# MicroMod-Ethernet-Function-Board-W5500.net
KiCad netlist of a schematic drawn in EAGLE
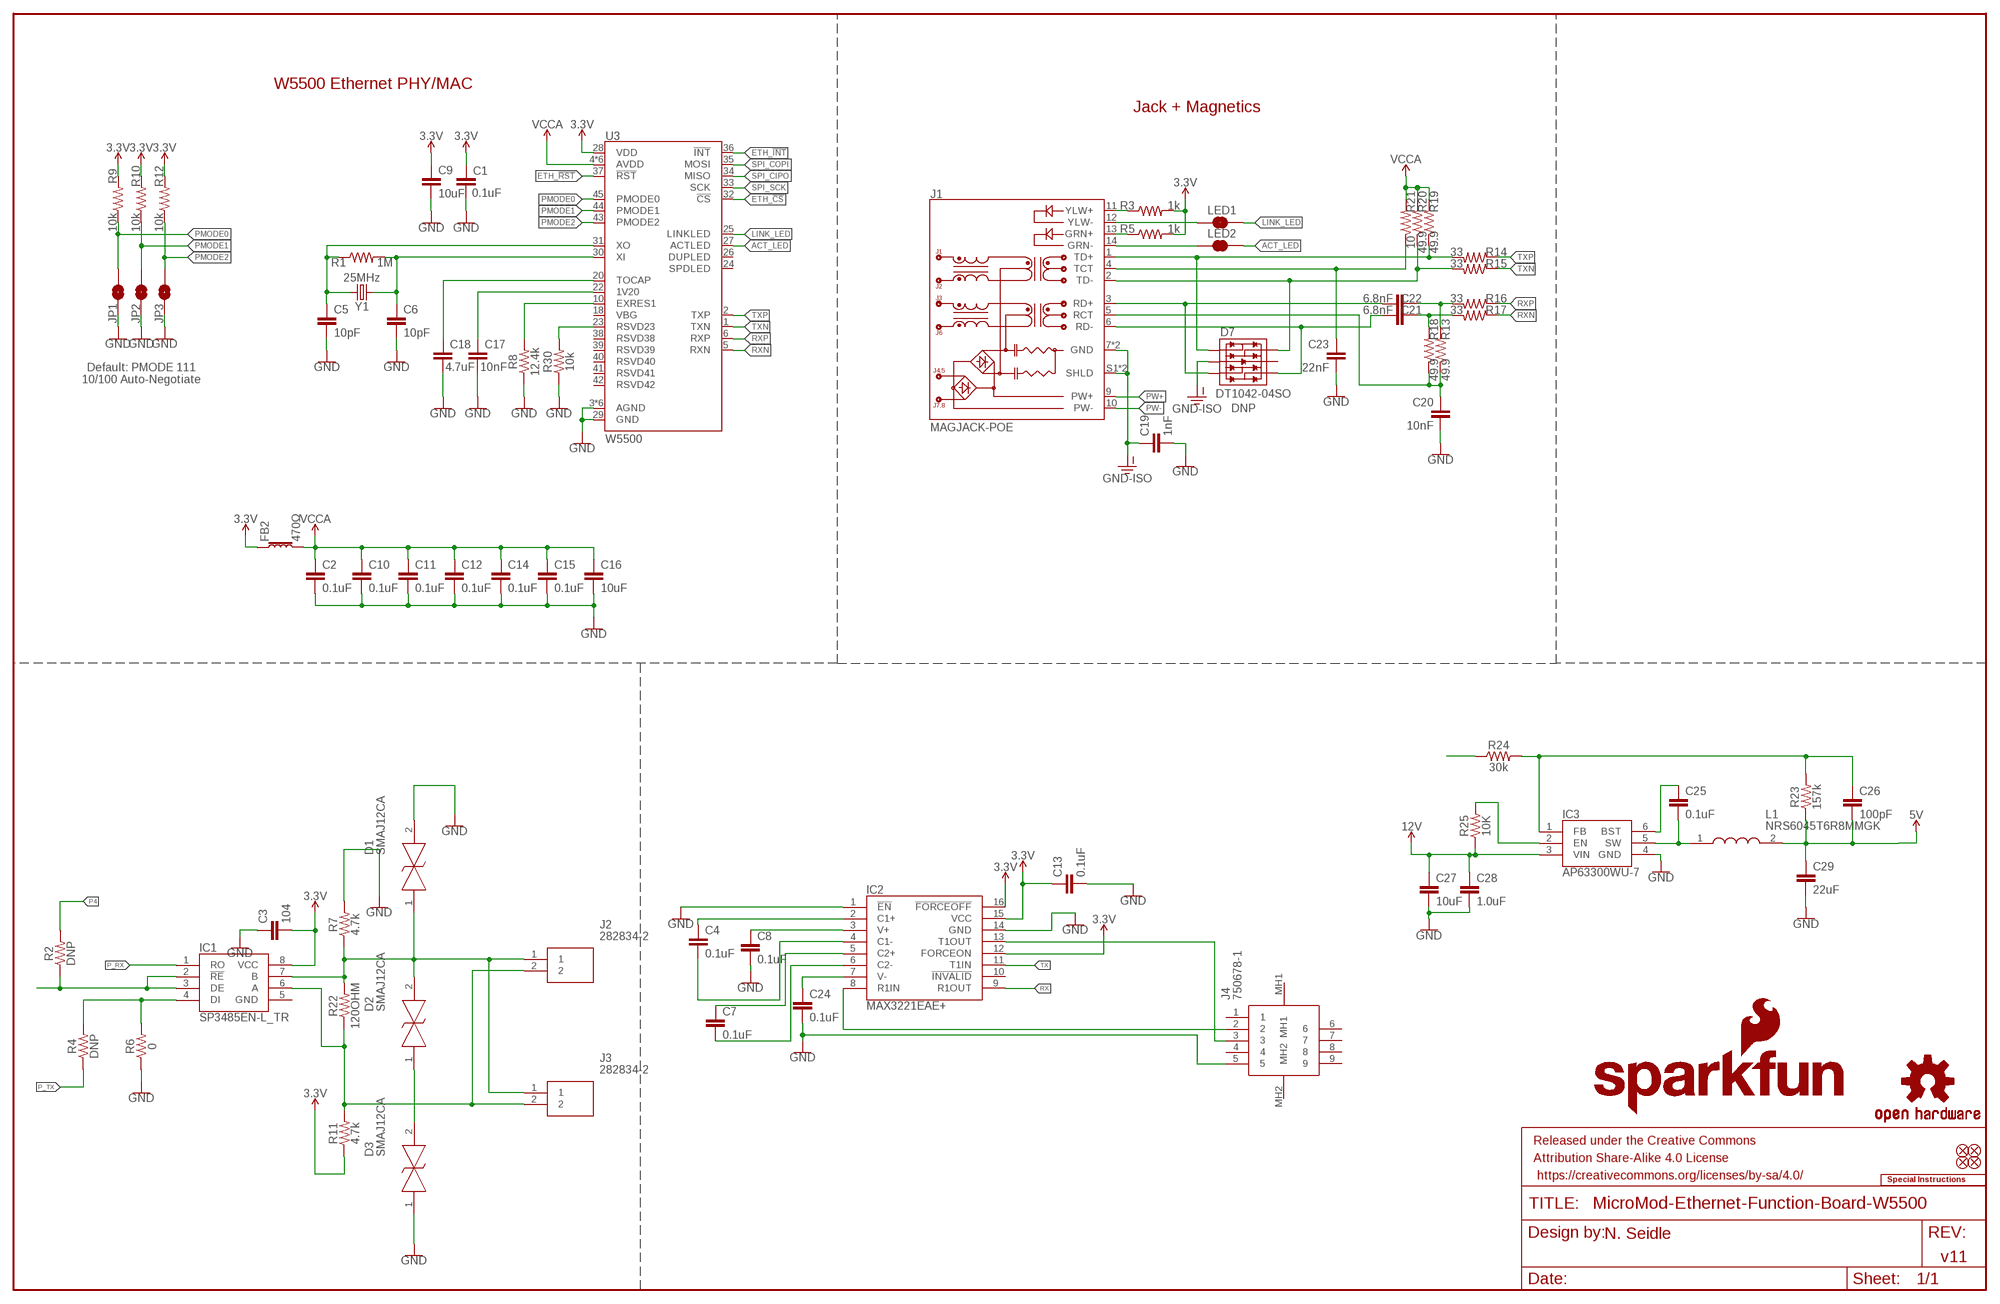
[diagram p0: schematic, sheet 1]

(export (version "E")
  (design (tool "Eeschema 10.0.6"))
  (components
    (comp (ref "C1")
      (value "0.1uF")
      (footprint "eagle-import:0603")
      (libsource (lib "eagle-import") (part "0.1UF-0603-25V-(+80/-20%)"))
    )
    (comp (ref "C2")
      (value "0.1uF")
      (footprint "eagle-import:0603")
      (libsource (lib "eagle-import") (part "0.1UF-0603-25V-5%"))
    )
    (comp (ref "C3")
      (value "104")
      (footprint "eagle-import:0402-TIGHT_NO_CREAM")
      (libsource (lib "eagle-import") (part "DNP-0402-TIGHT_NO_CREAM"))
    )
    (comp (ref "C4")
      (value "0.1uF")
      (footprint "eagle-import:0402-TIGHT")
      (libsource (lib "eagle-import") (part "0.1UF-0402T-10V-10%-X7R"))
    )
    (comp (ref "C5")
      (value "10pF")
      (footprint "eagle-import:0603")
      (libsource (lib "eagle-import") (part "10PF-0603-50V-5%"))
    )
    (comp (ref "C6")
      (value "10pF")
      (footprint "eagle-import:0603")
      (libsource (lib "eagle-import") (part "10PF-0603-50V-5%"))
    )
    (comp (ref "C7")
      (value "0.1uF")
      (footprint "eagle-import:0402-TIGHT")
      (libsource (lib "eagle-import") (part "0.1UF-0402T-10V-10%-X7R"))
    )
    (comp (ref "C8")
      (value "0.1uF")
      (footprint "eagle-import:0402-TIGHT")
      (libsource (lib "eagle-import") (part "0.1UF-0402T-10V-10%-X7R"))
    )
    (comp (ref "C9")
      (value "10uF")
      (footprint "eagle-import:0603")
      (libsource (lib "eagle-import") (part "10UF-0603-6.3V-20%"))
    )
    (comp (ref "C10")
      (value "0.1uF")
      (footprint "eagle-import:0603")
      (libsource (lib "eagle-import") (part "0.1UF-0603-25V-5%"))
    )
    (comp (ref "C11")
      (value "0.1uF")
      (footprint "eagle-import:0603")
      (libsource (lib "eagle-import") (part "0.1UF-0603-25V-5%"))
    )
    (comp (ref "C12")
      (value "0.1uF")
      (footprint "eagle-import:0603")
      (libsource (lib "eagle-import") (part "0.1UF-0603-25V-5%"))
    )
    (comp (ref "C13")
      (value "0.1uF")
      (footprint "eagle-import:0402-TIGHT")
      (libsource (lib "eagle-import") (part "0.1UF-0402T-10V-10%-X7R"))
    )
    (comp (ref "C14")
      (value "0.1uF")
      (footprint "eagle-import:0603")
      (libsource (lib "eagle-import") (part "0.1UF-0603-25V-5%"))
    )
    (comp (ref "C15")
      (value "0.1uF")
      (footprint "eagle-import:0603")
      (libsource (lib "eagle-import") (part "0.1UF-0603-25V-5%"))
    )
    (comp (ref "C16")
      (value "10uF")
      (footprint "eagle-import:0603")
      (libsource (lib "eagle-import") (part "10UF-0603-6.3V-20%"))
    )
    (comp (ref "C17")
      (value "10nF")
      (footprint "eagle-import:0603")
      (libsource (lib "eagle-import") (part "10NF-0603-50V-10%"))
    )
    (comp (ref "C18")
      (value "4.7uF")
      (footprint "eagle-import:0603")
      (libsource (lib "eagle-import") (part "4.7UF-0603-6.3V-(10%)"))
    )
    (comp (ref "C19")
      (value "1nF")
      (footprint "eagle-import:1206")
      (libsource (lib "eagle-import") (part "1.0NF/1000PF-1206-2KV-10%"))
    )
    (comp (ref "C20")
      (value "10nF")
      (footprint "eagle-import:0603")
      (libsource (lib "eagle-import") (part "10NF-0603-50V-10%"))
    )
    (comp (ref "C21")
      (value "6.8nF")
      (footprint "eagle-import:0603")
      (libsource (lib "eagle-import") (part "6.8NF/6800PF-0603-50V-5%"))
    )
    (comp (ref "C22")
      (value "6.8nF")
      (footprint "eagle-import:0603")
      (libsource (lib "eagle-import") (part "6.8NF/6800PF-0603-50V-5%"))
    )
    (comp (ref "C23")
      (value "22nF")
      (footprint "eagle-import:0603")
      (libsource (lib "eagle-import") (part "22NF/22,000PF-0603-50V-10%"))
    )
    (comp (ref "C24")
      (value "0.1uF")
      (footprint "eagle-import:0402-TIGHT")
      (libsource (lib "eagle-import") (part "0.1UF-0402T-10V-10%-X7R"))
    )
    (comp (ref "C25")
      (value "0.1uF")
      (footprint "eagle-import:0402-TIGHT")
      (libsource (lib "eagle-import") (part "0.1UF-0402T-10V-10%-X7R"))
    )
    (comp (ref "C26")
      (value "100pF")
      (footprint "eagle-import:0402-TIGHT")
      (libsource (lib "eagle-import") (part "100PF-0402T-50V-5%"))
    )
    (comp (ref "C27")
      (value "10uF")
      (footprint "eagle-import:0402-TIGHT")
      (libsource (lib "eagle-import") (part "10UF-0402T-6.3V-20%"))
    )
    (comp (ref "C28")
      (value "1.0uF")
      (footprint "eagle-import:0402-TIGHT")
      (libsource (lib "eagle-import") (part "1.0UF-0402T-16V-10%"))
    )
    (comp (ref "C29")
      (value "22uF")
      (footprint "eagle-import:0603")
      (libsource (lib "eagle-import") (part "22UF-0603-6.3V-20%"))
    )
    (comp (ref "D1")
      (value "SMAJ12CA")
      (footprint "eagle-import:DIONM5026X229N")
      (fields (field (name "MOUSER_PART_NUMBER") "576-SMAJ12CA"))
      (libsource (lib "eagle-import") (part "SMAJ12CA"))
    )
    (comp (ref "D2")
      (value "SMAJ12CA")
      (footprint "eagle-import:DIONM5026X229N")
      (fields (field (name "MOUSER_PART_NUMBER") "576-SMAJ12CA"))
      (libsource (lib "eagle-import") (part "SMAJ12CA"))
    )
    (comp (ref "D3")
      (value "SMAJ12CA")
      (footprint "eagle-import:DIONM5026X229N")
      (fields (field (name "MOUSER_PART_NUMBER") "576-SMAJ12CA"))
      (libsource (lib "eagle-import") (part "SMAJ12CA"))
    )
    (comp (ref "D7")
      (value "DT1042-04SO")
      (footprint "eagle-import:SOT-23-6")
      (libsource (lib "eagle-import") (part "TVS_DIODE_ARRAYSMD"))
    )
    (comp (ref "FB2")
      (value "470Ω")
      (footprint "eagle-import:0603")
      (libsource (lib "eagle-import") (part "FERRITE_BEAD-0603-470Ω-100MHZ-1A-200MILIΩ"))
    )
    (comp (ref "FD1")
      (value "FIDUCIALUFIDUCIAL")
      (footprint "eagle-import:FIDUCIAL-MICRO")
      (libsource (lib "eagle-import") (part "FIDUCIALUFIDUCIAL"))
    )
    (comp (ref "FD2")
      (value "FIDUCIALUFIDUCIAL")
      (footprint "eagle-import:FIDUCIAL-MICRO")
      (libsource (lib "eagle-import") (part "FIDUCIALUFIDUCIAL"))
    )
    (comp (ref "FD3")
      (value "FIDUCIALUFIDUCIAL")
      (footprint "eagle-import:FIDUCIAL-MICRO")
      (libsource (lib "eagle-import") (part "FIDUCIALUFIDUCIAL"))
    )
    (comp (ref "FD4")
      (value "FIDUCIALUFIDUCIAL")
      (footprint "eagle-import:FIDUCIAL-MICRO")
      (libsource (lib "eagle-import") (part "FIDUCIALUFIDUCIAL"))
    )
    (comp (ref "FRAME1")
      (value "FRAME-LEDGER")
      (footprint "eagle-import:CREATIVE_COMMONS")
      (libsource (lib "eagle-import") (part "FRAME-LEDGER"))
    )
    (comp (ref "IC1")
      (value "SP3485EN-L_TR")
      (footprint "eagle-import:SOIC127P600X175-8N")
      (fields
        (field (name "ARROW_PART_NUMBER") "SP3485EN-L/TR")
        (field (name "MOUSER_PART_NUMBER") "701-SP3485EN-L/TR")
      )
      (libsource (lib "eagle-import") (part "SP3485EN-L_TR"))
    )
    (comp (ref "IC2")
      (value "MAX3221EAE+")
      (footprint "eagle-import:SOP65P778X199-16N")
      (fields (field (name "MOUSER_PART_NUMBER") "700-MAX3221EAE"))
      (libsource (lib "eagle-import") (part "MAX3221EAE+"))
    )
    (comp (ref "IC3")
      (value "AP63300WU-7")
      (footprint "eagle-import:SOT95P280X90-6N")
      (fields (field (name "MOUSER_PART_NUMBER") "621-AP63300WU-7"))
      (libsource (lib "eagle-import") (part "AP63300WU-7"))
    )
    (comp (ref "J1")
      (value "MAGJACK-POE")
      (footprint "eagle-import:MAGJACK-SYM_LED")
      (libsource (lib "eagle-import") (part "MAGJACK-POE"))
    )
    (comp (ref "J2")
      (value "282834-2")
      (footprint "eagle-import:282834-2_1")
      (fields (field (name "MOUSER_PART_NUMBER") "571-282834-2"))
      (libsource (lib "eagle-import") (part "282834-2"))
    )
    (comp (ref "J3")
      (value "282834-2")
      (footprint "eagle-import:282834-2_1")
      (fields (field (name "MOUSER_PART_NUMBER") "571-282834-2"))
      (libsource (lib "eagle-import") (part "282834-2"))
    )
    (comp (ref "J4")
      (value "750678-1")
      (footprint "eagle-import:7506781")
      (fields (field (name "MOUSER_PART_NUMBER") "571-7506781"))
      (libsource (lib "eagle-import") (part "750678-1"))
    )
    (comp (ref "JP1")
      (value "JUMPER-SMT_2_NO_SILK")
      (footprint "eagle-import:SMT-JUMPER_2_NO_SILK")
      (libsource (lib "eagle-import") (part "JUMPER-SMT_2_NO_SILK"))
    )
    (comp (ref "JP2")
      (value "JUMPER-SMT_2_NO_SILK")
      (footprint "eagle-import:SMT-JUMPER_2_NO_SILK")
      (libsource (lib "eagle-import") (part "JUMPER-SMT_2_NO_SILK"))
    )
    (comp (ref "JP3")
      (value "JUMPER-SMT_2_NO_SILK")
      (footprint "eagle-import:SMT-JUMPER_2_NO_SILK")
      (libsource (lib "eagle-import") (part "JUMPER-SMT_2_NO_SILK"))
    )
    (comp (ref "L1")
      (value "NRS6045T6R8MMGK")
      (footprint "eagle-import:NRS6045T6R8MMGK")
      (fields (field (name "MOUSER_PART_NUMBER") "963-NRS6045T6R8MMGK"))
      (libsource (lib "eagle-import") (part "NRS6045T6R8MMGK"))
    )
    (comp (ref "LED1")
      (value "JUMPER-SMT_2_NC_TRACE_SILK")
      (footprint "eagle-import:SMT-JUMPER_2_NC_TRACE_SILK")
      (libsource (lib "eagle-import") (part "JUMPER-SMT_2_NC_TRACE_SILK"))
    )
    (comp (ref "LED2")
      (value "JUMPER-SMT_2_NC_TRACE_SILK")
      (footprint "eagle-import:SMT-JUMPER_2_NC_TRACE_SILK")
      (libsource (lib "eagle-import") (part "JUMPER-SMT_2_NC_TRACE_SILK"))
    )
    (comp (ref "LOGO1")
      (value "SFE_LOGO_NAME_FLAME.1_INCH")
      (footprint "eagle-import:SFE_LOGO_NAME_FLAME_.1")
      (libsource (lib "eagle-import") (part "SFE_LOGO_NAME_FLAME.1_INCH"))
    )
    (comp (ref "LOGO2")
      (value "SPECIAL_INSTRUCTIONS-ORDERING")
      (footprint "eagle-import:ORDERING_INSTRUCTIONS")
      (libsource (lib "eagle-import") (part "SPECIAL_INSTRUCTIONS-ORDERING"))
    )
    (comp (ref "LOGO3")
      (value "OSHW-LOGOMINI")
      (footprint "eagle-import:OSHW-LOGO-MINI")
      (libsource (lib "eagle-import") (part "OSHW-LOGOMINI"))
    )
    (comp (ref "R1")
      (value "1M")
      (footprint "eagle-import:0603")
      (libsource (lib "eagle-import") (part "1MOHM-0603-1/4W-5%"))
    )
    (comp (ref "R2")
      (value "DNP")
      (footprint "eagle-import:0402-TIGHT")
      (libsource (lib "eagle-import") (part "DNP-0402T"))
    )
    (comp (ref "R3")
      (value "1k")
      (footprint "eagle-import:0603")
      (libsource (lib "eagle-import") (part "1KOHM-0603-1/10W-1%"))
    )
    (comp (ref "R4")
      (value "DNP")
      (footprint "eagle-import:0402-TIGHT")
      (libsource (lib "eagle-import") (part "DNP-0402T"))
    )
    (comp (ref "R5")
      (value "1k")
      (footprint "eagle-import:0603")
      (libsource (lib "eagle-import") (part "1KOHM-0603-1/10W-1%"))
    )
    (comp (ref "R6")
      (value "0")
      (footprint "eagle-import:0402-TIGHT")
      (libsource (lib "eagle-import") (part "0OHM-0402T-1/10W"))
    )
    (comp (ref "R7")
      (value "4.7k")
      (footprint "eagle-import:0402-TIGHT")
      (libsource (lib "eagle-import") (part "4.7KOHM-0402T-1/16W-1%"))
    )
    (comp (ref "R8")
      (value "12.4k")
      (footprint "eagle-import:0603")
      (libsource (lib "eagle-import") (part "12.4KOHM-0603-1/10W-1%"))
    )
    (comp (ref "R9")
      (value "10k")
      (footprint "eagle-import:0603")
      (libsource (lib "eagle-import") (part "10KOHM-0603-1/10W-1%"))
    )
    (comp (ref "R10")
      (value "10k")
      (footprint "eagle-import:0603")
      (libsource (lib "eagle-import") (part "10KOHM-0603-1/10W-1%"))
    )
    (comp (ref "R11")
      (value "4.7k")
      (footprint "eagle-import:0402-TIGHT")
      (libsource (lib "eagle-import") (part "4.7KOHM-0402T-1/16W-1%"))
    )
    (comp (ref "R12")
      (value "10k")
      (footprint "eagle-import:0603")
      (libsource (lib "eagle-import") (part "10KOHM-0603-1/10W-1%"))
    )
    (comp (ref "R13")
      (value "49.9")
      (footprint "eagle-import:0603")
      (libsource (lib "eagle-import") (part "49.9OHM-0603-1/10W-1%"))
    )
    (comp (ref "R14")
      (value "33")
      (footprint "eagle-import:0603")
      (libsource (lib "eagle-import") (part "33OHM-0603-1/10W-1%"))
    )
    (comp (ref "R15")
      (value "33")
      (footprint "eagle-import:0603")
      (libsource (lib "eagle-import") (part "33OHM-0603-1/10W-1%"))
    )
    (comp (ref "R16")
      (value "33")
      (footprint "eagle-import:0603")
      (libsource (lib "eagle-import") (part "33OHM-0603-1/10W-1%"))
    )
    (comp (ref "R17")
      (value "33")
      (footprint "eagle-import:0603")
      (libsource (lib "eagle-import") (part "33OHM-0603-1/10W-1%"))
    )
    (comp (ref "R18")
      (value "49.9")
      (footprint "eagle-import:0603")
      (libsource (lib "eagle-import") (part "49.9OHM-0603-1/10W-1%"))
    )
    (comp (ref "R19")
      (value "49.9")
      (footprint "eagle-import:0603")
      (libsource (lib "eagle-import") (part "49.9OHM-0603-1/10W-1%"))
    )
    (comp (ref "R20")
      (value "49.9")
      (footprint "eagle-import:0603")
      (libsource (lib "eagle-import") (part "49.9OHM-0603-1/10W-1%"))
    )
    (comp (ref "R21")
      (value "10")
      (footprint "eagle-import:0603")
      (libsource (lib "eagle-import") (part "10OHM-0603-1/10W-1%"))
    )
    (comp (ref "R22")
      (value "120OHM")
      (footprint "eagle-import:0603")
      (libsource (lib "eagle-import") (part "120OHM"))
    )
    (comp (ref "R23")
      (value "157k")
      (footprint "eagle-import:0402-TIGHT")
      (libsource (lib "eagle-import") (part "DNP-0402T"))
    )
    (comp (ref "R24")
      (value "30k")
      (footprint "eagle-import:0402-TIGHT")
      (libsource (lib "eagle-import") (part "DNP-0402T"))
    )
    (comp (ref "R25")
      (value "10K")
      (footprint "eagle-import:0402-TIGHT")
      (libsource (lib "eagle-import") (part "10KOHM-0402-1/10W-0.1%"))
    )
    (comp (ref "R30")
      (value "10k")
      (footprint "eagle-import:0603")
      (libsource (lib "eagle-import") (part "10KOHM-0603-1/10W-1%"))
    )
    (comp (ref "U3")
      (value "W5500")
      (footprint "eagle-import:LQFP-48")
      (libsource (lib "eagle-import") (part "W5500"))
    )
    (comp (ref "Y1")
      (value "25MHz")
      (footprint "eagle-import:CRYSTAL-SMD-2.0X1.6MM")
      (libsource (lib "eagle-import") (part "CRYSTAL-25MHZ-SMD-2.0X1.6MM"))
    )
  )
  (nets
    (net (code "1") (name "/ETH_~{CS}") (class "Default")
      (node (ref "U3") (pin "32") (pinfunction "~{CS}_32") (pintype "bidirectional"))
    )
    (net (code "2") (name "/ETH_~{INT}") (class "Default")
      (node (ref "U3") (pin "36") (pinfunction "~{INT}_36") (pintype "bidirectional"))
    )
    (net (code "3") (name "/ETH_~{RST}") (class "Default")
      (node (ref "U3") (pin "37") (pinfunction "~{RST}_37") (pintype "bidirectional"))
    )
    (net (code "4") (name "3.3V") (class "Default")
      (node (ref "C1") (pin "1") (pinfunction "1_1") (pintype "passive"))
      (node (ref "C13") (pin "1") (pinfunction "1_1") (pintype "passive"))
      (node (ref "C3") (pin "2") (pinfunction "2_2") (pintype "passive"))
      (node (ref "C9") (pin "1") (pinfunction "1_1") (pintype "passive"))
      (node (ref "FB2") (pin "1") (pinfunction "1_1") (pintype "passive"))
      (node (ref "IC1") (pin "8") (pinfunction "VCC_8") (pintype "bidirectional"))
      (node (ref "IC2") (pin "12") (pinfunction "FORCEON_12") (pintype "bidirectional"))
      (node (ref "IC2") (pin "15") (pinfunction "VCC_15") (pintype "bidirectional"))
      (node (ref "IC2") (pin "16") (pinfunction "~{FORCEOFF}_16") (pintype "bidirectional"))
      (node (ref "R10") (pin "2") (pinfunction "2_2") (pintype "passive"))
      (node (ref "R11") (pin "1") (pinfunction "1_1") (pintype "passive"))
      (node (ref "R12") (pin "2") (pinfunction "2_2") (pintype "passive"))
      (node (ref "R3") (pin "2") (pinfunction "2_2") (pintype "passive"))
      (node (ref "R5") (pin "2") (pinfunction "2_2") (pintype "passive"))
      (node (ref "R9") (pin "2") (pinfunction "2_2") (pintype "passive"))
      (node (ref "U3") (pin "28") (pinfunction "VDD_28") (pintype "bidirectional"))
    )
    (net (code "5") (name "5V") (class "Default")
      (node (ref "C26") (pin "2") (pinfunction "2_2") (pintype "passive"))
      (node (ref "C29") (pin "1") (pinfunction "1_1") (pintype "passive"))
      (node (ref "L1") (pin "2") (pinfunction "2_2") (pintype "bidirectional"))
      (node (ref "R23") (pin "1") (pinfunction "1_1") (pintype "passive"))
    )
    (net (code "6") (name "12V") (class "Default")
      (node (ref "C27") (pin "1") (pinfunction "1_1") (pintype "passive"))
      (node (ref "C28") (pin "1") (pinfunction "1_1") (pintype "passive"))
      (node (ref "IC3") (pin "3") (pinfunction "VIN_3") (pintype "bidirectional"))
      (node (ref "R25") (pin "1") (pinfunction "1_1") (pintype "passive"))
    )
    (net (code "7") (name "ACT_LED") (class "Default")
      (node (ref "LED2") (pin "2") (pinfunction "2_2") (pintype "passive"))
      (node (ref "U3") (pin "27") (pinfunction "ACTLED_27") (pintype "bidirectional"))
    )
    (net (code "8") (name "GND") (class "Default")
      (node (ref "C1") (pin "2") (pinfunction "2_2") (pintype "passive"))
      (node (ref "C10") (pin "2") (pinfunction "2_2") (pintype "passive"))
      (node (ref "C11") (pin "2") (pinfunction "2_2") (pintype "passive"))
      (node (ref "C12") (pin "2") (pinfunction "2_2") (pintype "passive"))
      (node (ref "C13") (pin "2") (pinfunction "2_2") (pintype "passive"))
      (node (ref "C14") (pin "2") (pinfunction "2_2") (pintype "passive"))
      (node (ref "C15") (pin "2") (pinfunction "2_2") (pintype "passive"))
      (node (ref "C16") (pin "2") (pinfunction "2_2") (pintype "passive"))
      (node (ref "C17") (pin "2") (pinfunction "2_2") (pintype "passive"))
      (node (ref "C18") (pin "2") (pinfunction "2_2") (pintype "passive"))
      (node (ref "C19") (pin "2") (pinfunction "2_2") (pintype "passive"))
      (node (ref "C2") (pin "2") (pinfunction "2_2") (pintype "passive"))
      (node (ref "C20") (pin "2") (pinfunction "2_2") (pintype "passive"))
      (node (ref "C23") (pin "2") (pinfunction "2_2") (pintype "passive"))
      (node (ref "C24") (pin "2") (pinfunction "2_2") (pintype "passive"))
      (node (ref "C27") (pin "2") (pinfunction "2_2") (pintype "passive"))
      (node (ref "C28") (pin "2") (pinfunction "2_2") (pintype "passive"))
      (node (ref "C29") (pin "2") (pinfunction "2_2") (pintype "passive"))
      (node (ref "C3") (pin "1") (pinfunction "1_1") (pintype "passive"))
      (node (ref "C5") (pin "2") (pinfunction "2_2") (pintype "passive"))
      (node (ref "C6") (pin "2") (pinfunction "2_2") (pintype "passive"))
      (node (ref "C8") (pin "2") (pinfunction "2_2") (pintype "passive"))
      (node (ref "C9") (pin "2") (pinfunction "2_2") (pintype "passive"))
      (node (ref "D1") (pin "2") (pinfunction "2_2") (pintype "bidirectional"))
      (node (ref "D3") (pin "1") (pinfunction "1_1") (pintype "bidirectional"))
      (node (ref "IC2") (pin "1") (pinfunction "~{EN}_1") (pintype "bidirectional"))
      (node (ref "IC2") (pin "14") (pinfunction "GND_14") (pintype "bidirectional"))
      (node (ref "IC3") (pin "4") (pinfunction "GND_4") (pintype "bidirectional"))
      (node (ref "J4") (pin "5") (pinfunction "5_5") (pintype "bidirectional"))
      (node (ref "JP1") (pin "1") (pinfunction "1_1") (pintype "passive"))
      (node (ref "JP2") (pin "1") (pinfunction "1_1") (pintype "passive"))
      (node (ref "JP3") (pin "1") (pinfunction "1_1") (pintype "passive"))
      (node (ref "R30") (pin "1") (pinfunction "1_1") (pintype "passive"))
      (node (ref "R6") (pin "1") (pinfunction "1_1") (pintype "passive"))
      (node (ref "R7") (pin "2") (pinfunction "2_2") (pintype "passive"))
      (node (ref "R8") (pin "1") (pinfunction "1_1") (pintype "passive"))
      (node (ref "U3") (pin "14") (pinfunction "AGND_14") (pintype "bidirectional"))
      (node (ref "U3") (pin "16") (pinfunction "AGND_16") (pintype "bidirectional"))
      (node (ref "U3") (pin "19") (pinfunction "AGND_19") (pintype "bidirectional"))
      (node (ref "U3") (pin "29") (pinfunction "GND_29") (pintype "bidirectional"))
      (node (ref "U3") (pin "3") (pinfunction "AGND_3") (pintype "bidirectional"))
      (node (ref "U3") (pin "48") (pinfunction "AGND_48") (pintype "bidirectional"))
      (node (ref "U3") (pin "9") (pinfunction "AGND_9") (pintype "bidirectional"))
    )
    (net (code "9") (name "GND-ISO") (class "Default")
      (node (ref "C19") (pin "1") (pinfunction "1_1") (pintype "passive"))
      (node (ref "D7") (pin "2") (pinfunction "VSS_2") (pintype "bidirectional"))
      (node (ref "J1") (pin "7") (pinfunction "GND_7") (pintype "bidirectional"))
      (node (ref "J1") (pin "8") (pinfunction "GND_8") (pintype "bidirectional"))
      (node (ref "J1") (pin "S1") (pinfunction "SHLD_S1") (pintype "bidirectional"))
      (node (ref "J1") (pin "S2") (pinfunction "SHLD_S2") (pintype "bidirectional"))
    )
    (net (code "10") (name "LINK_LED") (class "Default")
      (node (ref "LED1") (pin "2") (pinfunction "2_2") (pintype "passive"))
      (node (ref "U3") (pin "25") (pinfunction "LINKLED_25") (pintype "bidirectional"))
    )
    (net (code "11") (name "Net-(C21-Pad1)") (class "Default")
      (node (ref "C21") (pin "1") (pinfunction "1_1") (pintype "passive"))
      (node (ref "R17") (pin "2") (pinfunction "2_2") (pintype "passive"))
      (node (ref "R18") (pin "2") (pinfunction "2_2") (pintype "passive"))
    )
    (net (code "12") (name "Net-(C22-Pad1)") (class "Default")
      (node (ref "C22") (pin "1") (pinfunction "1_1") (pintype "passive"))
      (node (ref "R13") (pin "2") (pinfunction "2_2") (pintype "passive"))
      (node (ref "R16") (pin "2") (pinfunction "2_2") (pintype "passive"))
    )
    (net (code "13") (name "Net-(D2-Pad1)") (class "Default")
      (node (ref "D2") (pin "1") (pinfunction "1_1") (pintype "bidirectional"))
      (node (ref "D3") (pin "2") (pinfunction "2_2") (pintype "bidirectional"))
    )
    (net (code "14") (name "Net-(D7-IO1)") (class "Default")
      (node (ref "D7") (pin "1") (pinfunction "IO1_1") (pintype "bidirectional"))
      (node (ref "J1") (pin "1") (pinfunction "TD+_1") (pintype "bidirectional"))
      (node (ref "R14") (pin "2") (pinfunction "2_2") (pintype "passive"))
      (node (ref "R19") (pin "1") (pinfunction "1_1") (pintype "passive"))
    )
    (net (code "15") (name "Net-(D7-IO2)") (class "Default")
      (node (ref "C22") (pin "2") (pinfunction "2_2") (pintype "passive"))
      (node (ref "D7") (pin "3") (pinfunction "IO2_3") (pintype "bidirectional"))
      (node (ref "J1") (pin "3") (pinfunction "RD+_3") (pintype "bidirectional"))
    )
    (net (code "16") (name "Net-(D7-IO3)") (class "Default")
      (node (ref "C21") (pin "2") (pinfunction "2_2") (pintype "passive"))
      (node (ref "D7") (pin "4") (pinfunction "IO3_4") (pintype "bidirectional"))
      (node (ref "J1") (pin "6") (pinfunction "RD-_6") (pintype "bidirectional"))
    )
    (net (code "17") (name "Net-(D7-IO4)") (class "Default")
      (node (ref "D7") (pin "6") (pinfunction "IO4_6") (pintype "bidirectional"))
      (node (ref "J1") (pin "2") (pinfunction "TD-_2") (pintype "bidirectional"))
      (node (ref "R15") (pin "2") (pinfunction "2_2") (pintype "passive"))
      (node (ref "R20") (pin "1") (pinfunction "1_1") (pintype "passive"))
    )
    (net (code "18") (name "Net-(IC1-A)") (class "Default")
      (node (ref "IC1") (pin "6") (pinfunction "A_6") (pintype "bidirectional"))
      (node (ref "J2") (pin "2") (pinfunction "2_2") (pintype "bidirectional"))
      (node (ref "J3") (pin "2") (pinfunction "2_2") (pintype "bidirectional"))
      (node (ref "R11") (pin "2") (pinfunction "2_2") (pintype "passive"))
      (node (ref "R22") (pin "1") (pinfunction "1_1") (pintype "passive"))
    )
    (net (code "19") (name "Net-(IC1-B)") (class "Default")
      (node (ref "D1") (pin "1") (pinfunction "1_1") (pintype "bidirectional"))
      (node (ref "D2") (pin "2") (pinfunction "2_2") (pintype "bidirectional"))
      (node (ref "IC1") (pin "7") (pinfunction "B_7") (pintype "bidirectional"))
      (node (ref "J2") (pin "1") (pinfunction "1_1") (pintype "bidirectional"))
      (node (ref "J3") (pin "1") (pinfunction "1_1") (pintype "bidirectional"))
      (node (ref "R22") (pin "2") (pinfunction "2_2") (pintype "passive"))
      (node (ref "R7") (pin "1") (pinfunction "1_1") (pintype "passive"))
    )
    (net (code "20") (name "Net-(IC1-DE)") (class "Default")
      (node (ref "IC1") (pin "2") (pinfunction "~{RE}_2") (pintype "bidirectional"))
      (node (ref "IC1") (pin "3") (pinfunction "DE_3") (pintype "bidirectional"))
      (node (ref "R2") (pin "1") (pinfunction "1_1") (pintype "passive"))
    )
    (net (code "21") (name "Net-(IC1-DI)") (class "Default")
      (node (ref "IC1") (pin "4") (pinfunction "DI_4") (pintype "bidirectional"))
      (node (ref "R4") (pin "2") (pinfunction "2_2") (pintype "passive"))
      (node (ref "R6") (pin "2") (pinfunction "2_2") (pintype "passive"))
    )
    (net (code "22") (name "Net-(IC2-C1+)") (class "Default")
      (node (ref "C4") (pin "1") (pinfunction "1_1") (pintype "passive"))
      (node (ref "IC2") (pin "2") (pinfunction "C1+_2") (pintype "bidirectional"))
    )
    (net (code "23") (name "Net-(IC2-C1-)") (class "Default")
      (node (ref "C4") (pin "2") (pinfunction "2_2") (pintype "passive"))
      (node (ref "IC2") (pin "4") (pinfunction "C1-_4") (pintype "bidirectional"))
    )
    (net (code "24") (name "Net-(IC2-C2+)") (class "Default")
      (node (ref "C7") (pin "1") (pinfunction "1_1") (pintype "passive"))
      (node (ref "IC2") (pin "5") (pinfunction "C2+_5") (pintype "bidirectional"))
    )
    (net (code "25") (name "Net-(IC2-C2-)") (class "Default")
      (node (ref "C7") (pin "2") (pinfunction "2_2") (pintype "passive"))
      (node (ref "IC2") (pin "6") (pinfunction "C2-_6") (pintype "bidirectional"))
    )
    (net (code "26") (name "Net-(IC2-R1IN)") (class "Default")
      (node (ref "IC2") (pin "8") (pinfunction "R1IN_8") (pintype "bidirectional"))
      (node (ref "J4") (pin "2") (pinfunction "2_2") (pintype "bidirectional"))
    )
    (net (code "27") (name "Net-(IC2-T1OUT)") (class "Default")
      (node (ref "IC2") (pin "13") (pinfunction "T1OUT_13") (pintype "bidirectional"))
      (node (ref "J4") (pin "3") (pinfunction "3_3") (pintype "bidirectional"))
    )
    (net (code "28") (name "Net-(IC2-V+)") (class "Default")
      (node (ref "C8") (pin "1") (pinfunction "1_1") (pintype "passive"))
      (node (ref "IC2") (pin "3") (pinfunction "V+_3") (pintype "bidirectional"))
    )
    (net (code "29") (name "Net-(IC2-V-)") (class "Default")
      (node (ref "C24") (pin "1") (pinfunction "1_1") (pintype "passive"))
      (node (ref "IC2") (pin "7") (pinfunction "V-_7") (pintype "bidirectional"))
    )
    (net (code "30") (name "Net-(IC3-BST)") (class "Default")
      (node (ref "C25") (pin "1") (pinfunction "1_1") (pintype "passive"))
      (node (ref "IC3") (pin "6") (pinfunction "BST_6") (pintype "bidirectional"))
    )
    (net (code "31") (name "Net-(IC3-EN)") (class "Default")
      (node (ref "IC3") (pin "2") (pinfunction "EN_2") (pintype "bidirectional"))
      (node (ref "R25") (pin "2") (pinfunction "2_2") (pintype "passive"))
    )
    (net (code "32") (name "Net-(IC3-FB)") (class "Default")
      (node (ref "C26") (pin "1") (pinfunction "1_1") (pintype "passive"))
      (node (ref "IC3") (pin "1") (pinfunction "FB_1") (pintype "bidirectional"))
      (node (ref "R23") (pin "2") (pinfunction "2_2") (pintype "passive"))
      (node (ref "R24") (pin "2") (pinfunction "2_2") (pintype "passive"))
    )
    (net (code "33") (name "Net-(IC3-SW)") (class "Default")
      (node (ref "C25") (pin "2") (pinfunction "2_2") (pintype "passive"))
      (node (ref "IC3") (pin "5") (pinfunction "SW_5") (pintype "bidirectional"))
      (node (ref "L1") (pin "1") (pinfunction "1_1") (pintype "bidirectional"))
    )
    (net (code "34") (name "Net-(J1-GRN+)") (class "Default")
      (node (ref "J1") (pin "13") (pinfunction "GRN+_13") (pintype "bidirectional"))
      (node (ref "R5") (pin "1") (pinfunction "1_1") (pintype "passive"))
    )
    (net (code "35") (name "Net-(J1-GRN-)") (class "Default")
      (node (ref "J1") (pin "14") (pinfunction "GRN-_14") (pintype "bidirectional"))
      (node (ref "LED2") (pin "1") (pinfunction "1_1") (pintype "passive"))
    )
    (net (code "36") (name "Net-(J1-RCT)") (class "Default")
      (node (ref "C20") (pin "1") (pinfunction "1_1") (pintype "passive"))
      (node (ref "J1") (pin "5") (pinfunction "RCT_5") (pintype "bidirectional"))
      (node (ref "R13") (pin "1") (pinfunction "1_1") (pintype "passive"))
      (node (ref "R18") (pin "1") (pinfunction "1_1") (pintype "passive"))
    )
    (net (code "37") (name "Net-(J1-TCT)") (class "Default")
      (node (ref "C23") (pin "1") (pinfunction "1_1") (pintype "passive"))
      (node (ref "J1") (pin "4") (pinfunction "TCT_4") (pintype "bidirectional"))
      (node (ref "R21") (pin "1") (pinfunction "1_1") (pintype "passive"))
    )
    (net (code "38") (name "Net-(J1-YLW+)") (class "Default")
      (node (ref "J1") (pin "11") (pinfunction "YLW+_11") (pintype "bidirectional"))
      (node (ref "R3") (pin "1") (pinfunction "1_1") (pintype "passive"))
    )
    (net (code "39") (name "Net-(J1-YLW-)") (class "Default")
      (node (ref "J1") (pin "12") (pinfunction "YLW-_12") (pintype "bidirectional"))
      (node (ref "LED1") (pin "1") (pinfunction "1_1") (pintype "passive"))
    )
    (net (code "40") (name "Net-(U3-1V20)") (class "Default")
      (node (ref "C17") (pin "1") (pinfunction "1_1") (pintype "passive"))
      (node (ref "U3") (pin "22") (pinfunction "1V20_22") (pintype "bidirectional"))
    )
    (net (code "41") (name "Net-(U3-EXRES1)") (class "Default")
      (node (ref "R8") (pin "2") (pinfunction "2_2") (pintype "passive"))
      (node (ref "U3") (pin "10") (pinfunction "EXRES1_10") (pintype "bidirectional"))
    )
    (net (code "42") (name "Net-(U3-RSVD23)") (class "Default")
      (node (ref "R30") (pin "2") (pinfunction "2_2") (pintype "passive"))
      (node (ref "U3") (pin "23") (pinfunction "RSVD23_23") (pintype "bidirectional"))
    )
    (net (code "43") (name "Net-(U3-TOCAP)") (class "Default")
      (node (ref "C18") (pin "1") (pinfunction "1_1") (pintype "passive"))
      (node (ref "U3") (pin "20") (pinfunction "TOCAP_20") (pintype "bidirectional"))
    )
    (net (code "44") (name "Net-(U3-XI)") (class "Default")
      (node (ref "C6") (pin "1") (pinfunction "1_1") (pintype "passive"))
      (node (ref "R1") (pin "2") (pinfunction "2_2") (pintype "passive"))
      (node (ref "U3") (pin "30") (pinfunction "XI_30") (pintype "bidirectional"))
      (node (ref "Y1") (pin "3") (pinfunction "2_3") (pintype "passive"))
    )
    (net (code "45") (name "Net-(U3-XO)") (class "Default")
      (node (ref "C5") (pin "1") (pinfunction "1_1") (pintype "passive"))
      (node (ref "R1") (pin "1") (pinfunction "1_1") (pintype "passive"))
      (node (ref "U3") (pin "31") (pinfunction "XO_31") (pintype "bidirectional"))
      (node (ref "Y1") (pin "1") (pinfunction "1_1") (pintype "passive"))
    )
    (net (code "46") (name "P4") (class "Default")
      (node (ref "R2") (pin "2") (pinfunction "2_2") (pintype "passive"))
    )
    (net (code "47") (name "PMODE0") (class "Default")
      (node (ref "JP1") (pin "2") (pinfunction "2_2") (pintype "passive"))
      (node (ref "R9") (pin "1") (pinfunction "1_1") (pintype "passive"))
      (node (ref "U3") (pin "45") (pinfunction "PMODE0_45") (pintype "bidirectional"))
    )
    (net (code "48") (name "PMODE1") (class "Default")
      (node (ref "JP2") (pin "2") (pinfunction "2_2") (pintype "passive"))
      (node (ref "R10") (pin "1") (pinfunction "1_1") (pintype "passive"))
      (node (ref "U3") (pin "44") (pinfunction "PMODE1_44") (pintype "bidirectional"))
    )
    (net (code "49") (name "PMODE2") (class "Default")
      (node (ref "JP3") (pin "2") (pinfunction "2_2") (pintype "passive"))
      (node (ref "R12") (pin "1") (pinfunction "1_1") (pintype "passive"))
      (node (ref "U3") (pin "43") (pinfunction "PMODE2_43") (pintype "bidirectional"))
    )
    (net (code "50") (name "PW+") (class "Default")
      (node (ref "J1") (pin "9") (pinfunction "PW+_9") (pintype "bidirectional"))
    )
    (net (code "51") (name "PW-") (class "Default")
      (node (ref "J1") (pin "10") (pinfunction "PW-_10") (pintype "bidirectional"))
    )
    (net (code "52") (name "P_RX") (class "Default")
      (node (ref "IC1") (pin "1") (pinfunction "RO_1") (pintype "bidirectional"))
    )
    (net (code "53") (name "P_TX") (class "Default")
      (node (ref "R4") (pin "1") (pinfunction "1_1") (pintype "passive"))
    )
    (net (code "54") (name "RX") (class "Default")
      (node (ref "IC2") (pin "9") (pinfunction "R1OUT_9") (pintype "bidirectional"))
    )
    (net (code "55") (name "RXN") (class "Default")
      (node (ref "R17") (pin "1") (pinfunction "1_1") (pintype "passive"))
      (node (ref "U3") (pin "5") (pinfunction "RXN_5") (pintype "bidirectional"))
    )
    (net (code "56") (name "RXP") (class "Default")
      (node (ref "R16") (pin "1") (pinfunction "1_1") (pintype "passive"))
      (node (ref "U3") (pin "6") (pinfunction "RXP_6") (pintype "bidirectional"))
    )
    (net (code "57") (name "SPI_CIPO") (class "Default")
      (node (ref "U3") (pin "34") (pinfunction "MISO_34") (pintype "bidirectional"))
    )
    (net (code "58") (name "SPI_COPI") (class "Default")
      (node (ref "U3") (pin "35") (pinfunction "MOSI_35") (pintype "bidirectional"))
    )
    (net (code "59") (name "SPI_SCK") (class "Default")
      (node (ref "U3") (pin "33") (pinfunction "SCK_33") (pintype "bidirectional"))
    )
    (net (code "60") (name "TX") (class "Default")
      (node (ref "IC2") (pin "11") (pinfunction "T1IN_11") (pintype "bidirectional"))
    )
    (net (code "61") (name "TXN") (class "Default")
      (node (ref "R15") (pin "1") (pinfunction "1_1") (pintype "passive"))
      (node (ref "U3") (pin "1") (pinfunction "TXN_1") (pintype "bidirectional"))
    )
    (net (code "62") (name "TXP") (class "Default")
      (node (ref "R14") (pin "1") (pinfunction "1_1") (pintype "passive"))
      (node (ref "U3") (pin "2") (pinfunction "TXP_2") (pintype "bidirectional"))
    )
    (net (code "63") (name "VCCA") (class "Default")
      (node (ref "C10") (pin "1") (pinfunction "1_1") (pintype "passive"))
      (node (ref "C11") (pin "1") (pinfunction "1_1") (pintype "passive"))
      (node (ref "C12") (pin "1") (pinfunction "1_1") (pintype "passive"))
      (node (ref "C14") (pin "1") (pinfunction "1_1") (pintype "passive"))
      (node (ref "C15") (pin "1") (pinfunction "1_1") (pintype "passive"))
      (node (ref "C16") (pin "1") (pinfunction "1_1") (pintype "passive"))
      (node (ref "C2") (pin "1") (pinfunction "1_1") (pintype "passive"))
      (node (ref "FB2") (pin "2") (pinfunction "2_2") (pintype "passive"))
      (node (ref "R19") (pin "2") (pinfunction "2_2") (pintype "passive"))
      (node (ref "R20") (pin "2") (pinfunction "2_2") (pintype "passive"))
      (node (ref "R21") (pin "2") (pinfunction "2_2") (pintype "passive"))
      (node (ref "U3") (pin "11") (pinfunction "AVDD_11") (pintype "bidirectional"))
      (node (ref "U3") (pin "15") (pinfunction "AVDD_15") (pintype "bidirectional"))
      (node (ref "U3") (pin "17") (pinfunction "AVDD_17") (pintype "bidirectional"))
      (node (ref "U3") (pin "21") (pinfunction "AVDD_21") (pintype "bidirectional"))
      (node (ref "U3") (pin "4") (pinfunction "AVDD_4") (pintype "bidirectional"))
      (node (ref "U3") (pin "8") (pinfunction "AVDD_8") (pintype "bidirectional"))
    )
    (net (code "64") (name "unconnected-(D7-VCC-Pad5)") (class "Default")
      (node (ref "D7") (pin "5") (pinfunction "VCC_5") (pintype "bidirectional"))
    )
    (net (code "65") (name "unconnected-(IC1-GND-Pad5)") (class "Default")
      (node (ref "IC1") (pin "5") (pinfunction "GND_5") (pintype "bidirectional"))
    )
    (net (code "66") (name "unconnected-(IC2-~{INVALID}-Pad10)") (class "Default")
      (node (ref "IC2") (pin "10") (pinfunction "~{INVALID}_10") (pintype "bidirectional"))
    )
    (net (code "67") (name "unconnected-(J4-Pad1)") (class "Default")
      (node (ref "J4") (pin "1") (pinfunction "1_1") (pintype "bidirectional"))
    )
    (net (code "68") (name "unconnected-(J4-Pad4)") (class "Default")
      (node (ref "J4") (pin "4") (pinfunction "4_4") (pintype "bidirectional"))
    )
    (net (code "69") (name "unconnected-(J4-Pad6)") (class "Default")
      (node (ref "J4") (pin "6") (pinfunction "6_6") (pintype "bidirectional"))
    )
    (net (code "70") (name "unconnected-(J4-Pad7)") (class "Default")
      (node (ref "J4") (pin "7") (pinfunction "7_7") (pintype "bidirectional"))
    )
    (net (code "71") (name "unconnected-(J4-Pad8)") (class "Default")
      (node (ref "J4") (pin "8") (pinfunction "8_8") (pintype "bidirectional"))
    )
    (net (code "72") (name "unconnected-(J4-Pad9)") (class "Default")
      (node (ref "J4") (pin "9") (pinfunction "9_9") (pintype "bidirectional"))
    )
    (net (code "73") (name "unconnected-(J4-PadMH1)") (class "Default")
      (node (ref "J4") (pin "MH1") (pinfunction "MH1_MH1") (pintype "bidirectional"))
    )
    (net (code "74") (name "unconnected-(J4-PadMH2)") (class "Default")
      (node (ref "J4") (pin "MH2") (pinfunction "MH2_MH2") (pintype "bidirectional"))
    )
    (net (code "75") (name "unconnected-(R24-Pad1)") (class "Default")
      (node (ref "R24") (pin "1") (pinfunction "1_1") (pintype "passive"))
    )
    (net (code "76") (name "unconnected-(U3-DUPLED-Pad26)") (class "Default")
      (node (ref "U3") (pin "26") (pinfunction "DUPLED_26") (pintype "bidirectional"))
    )
    (net (code "77") (name "unconnected-(U3-RSVD38-Pad38)") (class "Default")
      (node (ref "U3") (pin "38") (pinfunction "RSVD38_38") (pintype "bidirectional"))
    )
    (net (code "78") (name "unconnected-(U3-RSVD39-Pad39)") (class "Default")
      (node (ref "U3") (pin "39") (pinfunction "RSVD39_39") (pintype "bidirectional"))
    )
    (net (code "79") (name "unconnected-(U3-RSVD40-Pad40)") (class "Default")
      (node (ref "U3") (pin "40") (pinfunction "RSVD40_40") (pintype "bidirectional"))
    )
    (net (code "80") (name "unconnected-(U3-RSVD41-Pad41)") (class "Default")
      (node (ref "U3") (pin "41") (pinfunction "RSVD41_41") (pintype "bidirectional"))
    )
    (net (code "81") (name "unconnected-(U3-RSVD42-Pad42)") (class "Default")
      (node (ref "U3") (pin "42") (pinfunction "RSVD42_42") (pintype "bidirectional"))
    )
    (net (code "82") (name "unconnected-(U3-SPDLED-Pad24)") (class "Default")
      (node (ref "U3") (pin "24") (pinfunction "SPDLED_24") (pintype "bidirectional"))
    )
    (net (code "83") (name "unconnected-(U3-VBG-Pad18)") (class "Default")
      (node (ref "U3") (pin "18") (pinfunction "VBG_18") (pintype "bidirectional"))
    )
  )
)
